# design.net
KiCad netlist of a schematic drawn in Altium Designer
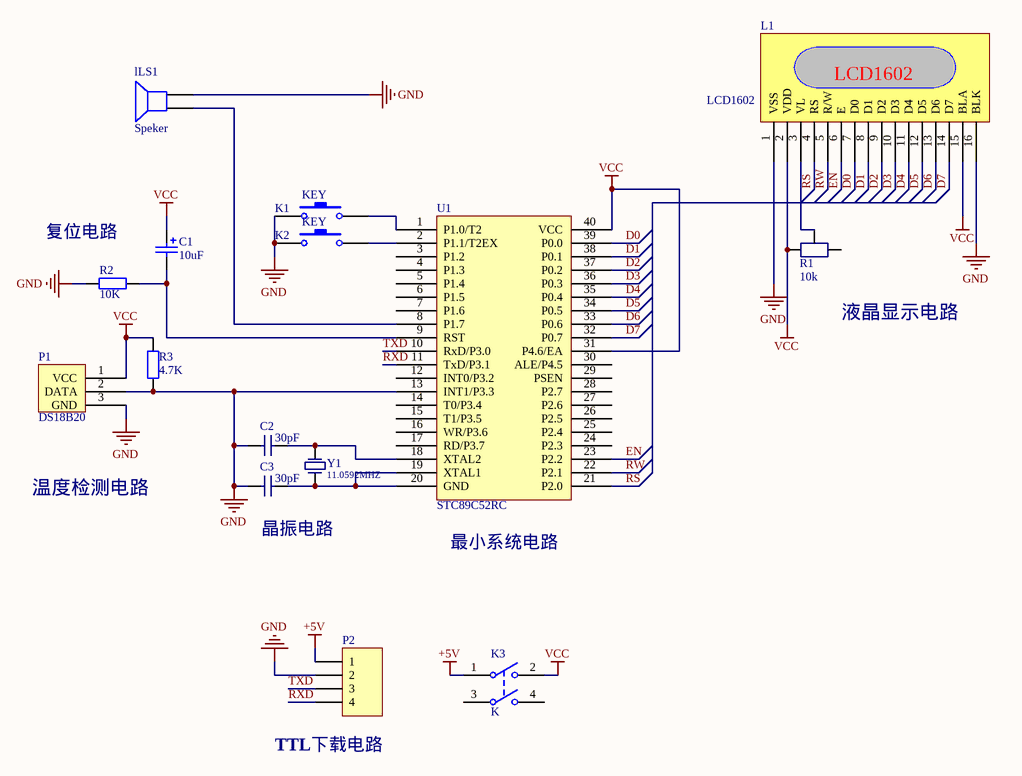
[diagram p0: 原理图.SchDoc]

(export (version "E")
  (design (tool "Eeschema 10.0.6"))
  (components
    (comp (ref "C1")
      (value "10uF")
      (footprint "cap4")
      (fields (field (name "Comment") "Cap-polarity"))
      (libsource (lib "General Component") (part "Cap-polarity"))
    )
    (comp (ref "C2")
      (value "30pF")
      (footprint "cap-2.545")
      (fields (field (name "Comment") "Cap"))
      (libsource (lib "General Component") (part "Cap"))
    )
    (comp (ref "C3")
      (value "30pF")
      (footprint "cap-2.545")
      (fields (field (name "Comment") "Cap"))
      (libsource (lib "General Component") (part "Cap"))
    )
    (comp (ref "K1") (value "KEY2") (footprint "KEY4") (libsource (lib "General Component") (part "KEY2")))
    (comp (ref "K2") (value "KEY2") (footprint "KEY4") (libsource (lib "General Component") (part "KEY2")))
    (comp (ref "K3")
      (value "K")
      (footprint "Switch-Single")
      (libsource (lib "General Component") (part "Switch-Single"))
    )
    (comp (ref "L1")
      (value "LCD1602")
      (footprint "LCD1602")
      (libsource (lib "General Component") (part "LCD1602"))
    )
    (comp (ref "lLS1")
      (value "Speker")
      (footprint "SPK-interface")
      (description "Loudspeaker")
      (libsource (lib "General Component") (part "Speker"))
    )
    (comp (ref "P1")
      (value "DS18B20")
      (footprint "PNP")
      (libsource (lib "General Component") (part "DS18B20"))
    )
    (comp (ref "P2")
      (value "Header 4")
      (footprint "HDR1X4")
      (description "Header, 4-Pin")
      (fields (field (name "PUBLISHER") "Altium Limited"))
      (libsource (lib "Miscellaneous Connectors") (part "Header 4"))
    )
    (comp (ref "R1")
      (value "10k")
      (footprint "RES1")
      (fields (field (name "Comment") "RES1"))
      (libsource (lib "General Component") (part "RES1"))
    )
    (comp (ref "R2")
      (value "RES")
      (footprint "RES2 AXIAL-0.4")
      (fields (field (name "RES") "10K"))
      (libsource (lib "") (part "RES_1"))
    )
    (comp (ref "R3")
      (value "RES")
      (footprint "RES2 AXIAL-0.4")
      (fields (field (name "RES") "4.7K"))
      (libsource (lib "General Component") (part "RES"))
    )
    (comp (ref "U1")
      (value "STC89C52RC")
      (footprint "DIP-40")
      (description "DIP40")
      (libsource (lib "chipset") (part "STC89C52RC"))
    )
    (comp (ref "Y1")
      (value "11.0592MHZ")
      (footprint "XALT2")
      (fields (field (name "Comment") "XTAL"))
      (libsource (lib "General Component") (part "XTAL"))
    )
  )
  (nets
    (net (code "1") (name "+5V") (class "Default")
      (node (ref "K3") (pin "1") (pintype "passive"))
      (node (ref "P2") (pin "1") (pinfunction "1_1") (pintype "passive"))
    )
    (net (code "2") (name "/D0") (class "Default")
      (node (ref "L1") (pin "7") (pinfunction "D0_7") (pintype "passive"))
      (node (ref "U1") (pin "39") (pinfunction "P0.0_39") (pintype "passive"))
    )
    (net (code "3") (name "/D1") (class "Default")
      (node (ref "L1") (pin "8") (pinfunction "D1_8") (pintype "passive"))
      (node (ref "U1") (pin "38") (pinfunction "P0.1_38") (pintype "passive"))
    )
    (net (code "4") (name "/D2") (class "Default")
      (node (ref "L1") (pin "9") (pinfunction "D2_9") (pintype "passive"))
      (node (ref "U1") (pin "37") (pinfunction "P0.2_37") (pintype "passive"))
    )
    (net (code "5") (name "/D3") (class "Default")
      (node (ref "L1") (pin "10") (pinfunction "D3_10") (pintype "passive"))
      (node (ref "U1") (pin "36") (pinfunction "P0.3_36") (pintype "passive"))
    )
    (net (code "6") (name "/D4") (class "Default")
      (node (ref "L1") (pin "11") (pinfunction "D4_11") (pintype "passive"))
      (node (ref "U1") (pin "35") (pinfunction "P0.4_35") (pintype "passive"))
    )
    (net (code "7") (name "/D5") (class "Default")
      (node (ref "L1") (pin "12") (pinfunction "D5_12") (pintype "passive"))
      (node (ref "U1") (pin "34") (pinfunction "P0.5_34") (pintype "passive"))
    )
    (net (code "8") (name "/D6") (class "Default")
      (node (ref "L1") (pin "13") (pinfunction "D6_13") (pintype "passive"))
      (node (ref "U1") (pin "33") (pinfunction "P0.6_33") (pintype "passive"))
    )
    (net (code "9") (name "/D7") (class "Default")
      (node (ref "L1") (pin "14") (pinfunction "D7_14") (pintype "passive"))
      (node (ref "U1") (pin "32") (pinfunction "P0.7_32") (pintype "passive"))
    )
    (net (code "10") (name "/EN") (class "Default")
      (node (ref "L1") (pin "6") (pinfunction "E_6") (pintype "passive"))
      (node (ref "U1") (pin "23") (pinfunction "P2.2_23") (pintype "passive"))
    )
    (net (code "11") (name "/RS") (class "Default")
      (node (ref "L1") (pin "4") (pinfunction "RS_4") (pintype "passive"))
      (node (ref "U1") (pin "21") (pinfunction "P2.0_21") (pintype "passive"))
    )
    (net (code "12") (name "/RW") (class "Default")
      (node (ref "L1") (pin "5") (pinfunction "R/W_5") (pintype "passive"))
      (node (ref "U1") (pin "22") (pinfunction "P2.1_22") (pintype "passive"))
    )
    (net (code "13") (name "/RXD") (class "Default")
      (node (ref "P2") (pin "4") (pinfunction "4_4") (pintype "passive"))
      (node (ref "U1") (pin "11") (pinfunction "TxD/P3.1_11") (pintype "passive"))
    )
    (net (code "14") (name "/TXD") (class "Default")
      (node (ref "P2") (pin "3") (pinfunction "3_3") (pintype "passive"))
      (node (ref "U1") (pin "10") (pinfunction "RxD/P3.0_10") (pintype "passive"))
    )
    (net (code "15") (name "GND") (class "Default")
      (node (ref "C2") (pin "1") (pintype "passive"))
      (node (ref "C3") (pin "1") (pintype "passive"))
      (node (ref "K1") (pin "1") (pinfunction "1_1") (pintype "passive"))
      (node (ref "K2") (pin "1") (pinfunction "1_1") (pintype "passive"))
      (node (ref "L1") (pin "1") (pinfunction "VSS_1") (pintype "power_in"))
      (node (ref "L1") (pin "16") (pinfunction "BLK_16") (pintype "passive"))
      (node (ref "P1") (pin "2") (pinfunction "DATA_2") (pintype "passive"))
      (node (ref "P1") (pin "3") (pinfunction "GND_3") (pintype "passive"))
      (node (ref "P2") (pin "2") (pinfunction "2_2") (pintype "passive"))
      (node (ref "R2") (pin "1") (pinfunction "1_1") (pintype "passive"))
      (node (ref "R3") (pin "2") (pinfunction "2_2") (pintype "passive"))
      (node (ref "U1") (pin "13") (pinfunction "INT1/P3.3_13") (pintype "passive"))
      (node (ref "lLS1") (pin "2") (pinfunction "2_2") (pintype "passive"))
    )
    (net (code "16") (name "Net-(L1-VL)") (class "Default")
      (node (ref "L1") (pin "3") (pinfunction "VL_3") (pintype "passive"))
      (node (ref "R1") (pin "2") (pintype "passive"))
    )
    (net (code "17") (name "Net-(U1-GND)") (class "Default")
      (node (ref "C3") (pin "2") (pintype "passive"))
      (node (ref "U1") (pin "19") (pinfunction "XTAL1_19") (pintype "passive"))
      (node (ref "U1") (pin "20") (pinfunction "GND_20") (pintype "power_in"))
      (node (ref "Y1") (pin "1") (pintype "passive"))
    )
    (net (code "18") (name "Net-(U1-P1.0{slash}T2)") (class "Default")
      (node (ref "K1") (pin "2") (pinfunction "2_2") (pintype "passive"))
      (node (ref "U1") (pin "1") (pinfunction "P1.0/T2_1") (pintype "passive"))
    )
    (net (code "19") (name "Net-(U1-P1.1{slash}T2EX)") (class "Default")
      (node (ref "K2") (pin "2") (pinfunction "2_2") (pintype "passive"))
      (node (ref "U1") (pin "2") (pinfunction "P1.1/T2EX_2") (pintype "passive"))
    )
    (net (code "20") (name "Net-(U1-P1.7)") (class "Default")
      (node (ref "U1") (pin "8") (pinfunction "P1.7_8") (pintype "passive"))
      (node (ref "lLS1") (pin "1") (pinfunction "1_1") (pintype "passive"))
    )
    (net (code "21") (name "Net-(U1-RST)") (class "Default")
      (node (ref "C1") (pin "2") (pinfunction "2_2") (pintype "passive"))
      (node (ref "R2") (pin "2") (pinfunction "2_2") (pintype "passive"))
      (node (ref "U1") (pin "9") (pinfunction "RST_9") (pintype "passive"))
    )
    (net (code "22") (name "Net-(U1-XTAL2)") (class "Default")
      (node (ref "C2") (pin "2") (pintype "passive"))
      (node (ref "U1") (pin "18") (pinfunction "XTAL2_18") (pintype "passive"))
      (node (ref "Y1") (pin "2") (pintype "passive"))
    )
    (net (code "23") (name "VCC") (class "Default")
      (node (ref "C1") (pin "1") (pinfunction "1_1") (pintype "passive"))
      (node (ref "K3") (pin "2") (pinfunction "NO1_2") (pintype "passive"))
      (node (ref "L1") (pin "15") (pinfunction "BLA_15") (pintype "passive"))
      (node (ref "L1") (pin "2") (pinfunction "VDD_2") (pintype "passive"))
      (node (ref "P1") (pin "1") (pinfunction "VCC_1") (pintype "passive"))
      (node (ref "R1") (pin "1") (pintype "passive"))
      (node (ref "R3") (pin "1") (pinfunction "1_1") (pintype "passive"))
      (node (ref "U1") (pin "31") (pinfunction "P4.6/EA_31") (pintype "passive"))
      (node (ref "U1") (pin "40") (pinfunction "VCC_40") (pintype "power_in"))
    )
    (net (code "24") (name "unconnected-(K3-COMMON2-Pad3)") (class "Default")
      (node (ref "K3") (pin "3") (pinfunction "COMMON2_3") (pintype "passive"))
    )
    (net (code "25") (name "unconnected-(K3-NO2-Pad4)") (class "Default")
      (node (ref "K3") (pin "4") (pinfunction "NO2_4") (pintype "passive"))
    )
    (net (code "26") (name "unconnected-(R1-Pad3)") (class "Default")
      (node (ref "R1") (pin "3") (pintype "passive"))
    )
    (net (code "27") (name "unconnected-(U1-ALE{slash}P4.5-Pad30)") (class "Default")
      (node (ref "U1") (pin "30") (pinfunction "ALE/P4.5_30") (pintype "passive"))
    )
    (net (code "28") (name "unconnected-(U1-INT0{slash}P3.2-Pad12)") (class "Default")
      (node (ref "U1") (pin "12") (pinfunction "INT0/P3.2_12") (pintype "passive"))
    )
    (net (code "29") (name "unconnected-(U1-P1.2-Pad3)") (class "Default")
      (node (ref "U1") (pin "3") (pinfunction "P1.2_3") (pintype "passive"))
    )
    (net (code "30") (name "unconnected-(U1-P1.3-Pad4)") (class "Default")
      (node (ref "U1") (pin "4") (pinfunction "P1.3_4") (pintype "passive"))
    )
    (net (code "31") (name "unconnected-(U1-P1.4-Pad5)") (class "Default")
      (node (ref "U1") (pin "5") (pinfunction "P1.4_5") (pintype "passive"))
    )
    (net (code "32") (name "unconnected-(U1-P1.5-Pad6)") (class "Default")
      (node (ref "U1") (pin "6") (pinfunction "P1.5_6") (pintype "passive"))
    )
    (net (code "33") (name "unconnected-(U1-P1.6-Pad7)") (class "Default")
      (node (ref "U1") (pin "7") (pinfunction "P1.6_7") (pintype "passive"))
    )
    (net (code "34") (name "unconnected-(U1-P2.3-Pad24)") (class "Default")
      (node (ref "U1") (pin "24") (pinfunction "P2.3_24") (pintype "passive"))
    )
    (net (code "35") (name "unconnected-(U1-P2.4-Pad25)") (class "Default")
      (node (ref "U1") (pin "25") (pinfunction "P2.4_25") (pintype "passive"))
    )
    (net (code "36") (name "unconnected-(U1-P2.5-Pad26)") (class "Default")
      (node (ref "U1") (pin "26") (pinfunction "P2.5_26") (pintype "passive"))
    )
    (net (code "37") (name "unconnected-(U1-P2.6-Pad27)") (class "Default")
      (node (ref "U1") (pin "27") (pinfunction "P2.6_27") (pintype "passive"))
    )
    (net (code "38") (name "unconnected-(U1-P2.7-Pad28)") (class "Default")
      (node (ref "U1") (pin "28") (pinfunction "P2.7_28") (pintype "passive"))
    )
    (net (code "39") (name "unconnected-(U1-PSEN-Pad29)") (class "Default")
      (node (ref "U1") (pin "29") (pinfunction "PSEN_29") (pintype "passive"))
    )
    (net (code "40") (name "unconnected-(U1-RD{slash}P3.7-Pad17)") (class "Default")
      (node (ref "U1") (pin "17") (pinfunction "RD/P3.7_17") (pintype "passive"))
    )
    (net (code "41") (name "unconnected-(U1-T0{slash}P3.4-Pad14)") (class "Default")
      (node (ref "U1") (pin "14") (pinfunction "T0/P3.4_14") (pintype "passive"))
    )
    (net (code "42") (name "unconnected-(U1-T1{slash}P3.5-Pad15)") (class "Default")
      (node (ref "U1") (pin "15") (pinfunction "T1/P3.5_15") (pintype "passive"))
    )
    (net (code "43") (name "unconnected-(U1-WR{slash}P3.6-Pad16)") (class "Default")
      (node (ref "U1") (pin "16") (pinfunction "WR/P3.6_16") (pintype "passive"))
    )
  )
)
